# neopixel_design_block.net
KiCad netlist of a schematic drawn in EAGLE
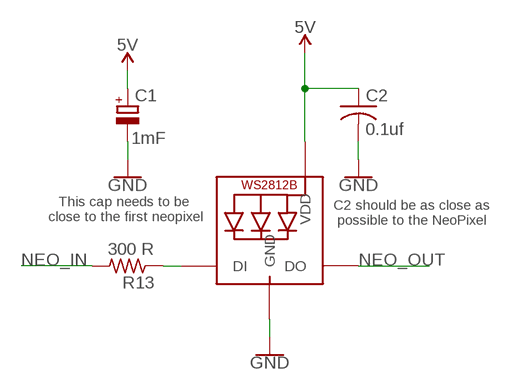
[diagram p0: schematic, sheet 1]

(export (version "E")
  (design (tool "Eeschema 10.0.6"))
  (components
    (comp (ref "C1")
      (value "1mF")
      (footprint "eagle-import:153CLV-1010")
      (libsource (lib "eagle-import") (part "CPOL-EU153CLV-1010"))
    )
    (comp (ref "C2")
      (value "0.1uf")
      (footprint "eagle-import:C0805K")
      (libsource (lib "eagle-import") (part "C-USC0805K"))
    )
    (comp (ref "NEO1")
      (value "WS2812B5050")
      (footprint "eagle-import:WS2812B")
      (libsource (lib "eagle-import") (part "WS2812B5050"))
    )
    (comp (ref "R13")
      (value "300 R")
      (footprint "eagle-import:R0805")
      (libsource (lib "eagle-import") (part "R-US_R0805"))
    )
  )
  (nets
    (net (code "1") (name "/NEO_IN") (class "Default")
      (node (ref "R13") (pin "2") (pinfunction "2_2") (pintype "passive"))
    )
    (net (code "2") (name "/NEO_OUT") (class "Default")
      (node (ref "NEO1") (pin "2-DOUT") (pinfunction "DO_2-DOUT") (pintype "output"))
    )
    (net (code "3") (name "5V") (class "Default")
      (node (ref "C1") (pin "+") (pinfunction "+_+") (pintype "passive"))
      (node (ref "C2") (pin "1") (pinfunction "1_1") (pintype "passive"))
      (node (ref "NEO1") (pin "1-VDD") (pinfunction "VDD_1-VDD") (pintype "power_in"))
    )
    (net (code "4") (name "GND") (class "Default")
      (node (ref "C1") (pin "-") (pinfunction "-_-") (pintype "passive"))
      (node (ref "C2") (pin "2") (pinfunction "2_2") (pintype "passive"))
      (node (ref "NEO1") (pin "3-GND") (pinfunction "GND_3-GND") (pintype "power_in"))
    )
    (net (code "5") (name "Net-(NEO1-DI)") (class "Default")
      (node (ref "NEO1") (pin "4-DIN") (pinfunction "DI_4-DIN") (pintype "input"))
      (node (ref "R13") (pin "1") (pinfunction "1_1") (pintype "passive"))
    )
  )
)
